# 2lboard.net
KiCad netlist of a schematic drawn in EAGLE
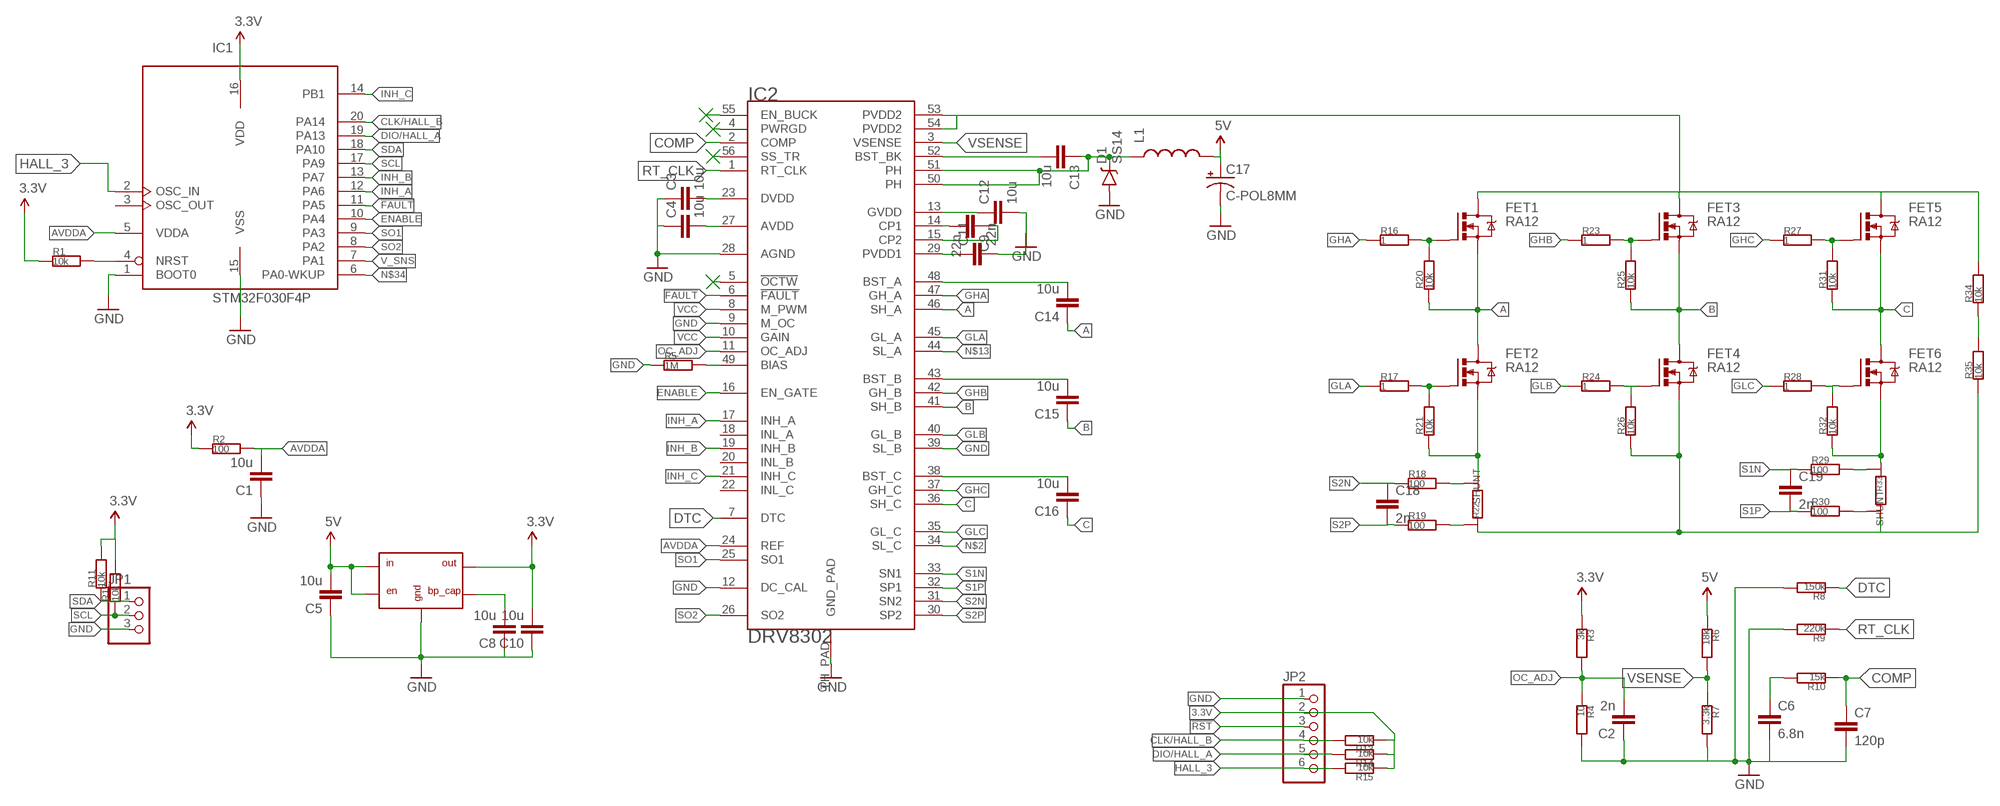
[diagram p0: schematic, sheet 1]

(export (version "E")
  (design (tool "Eeschema 10.0.6"))
  (components
    (comp (ref "C1")
      (value "10u")
      (footprint "eagle-import:C0805")
      (libsource (lib "eagle-import") (part "CC0805"))
    )
    (comp (ref "C2")
      (value "2n")
      (footprint "eagle-import:C0805")
      (libsource (lib "eagle-import") (part "CC0805"))
    )
    (comp (ref "C3")
      (value "10u")
      (footprint "eagle-import:C0805")
      (libsource (lib "eagle-import") (part "CC0805"))
    )
    (comp (ref "C4")
      (value "10u")
      (footprint "eagle-import:C0805")
      (libsource (lib "eagle-import") (part "CC0805"))
    )
    (comp (ref "C5")
      (value "10u")
      (footprint "eagle-import:C0805")
      (libsource (lib "eagle-import") (part "CC0805"))
    )
    (comp (ref "C6")
      (value "6.8n")
      (footprint "eagle-import:C0805")
      (libsource (lib "eagle-import") (part "CC0805"))
    )
    (comp (ref "C7")
      (value "120p")
      (footprint "eagle-import:C0805")
      (libsource (lib "eagle-import") (part "CC0805"))
    )
    (comp (ref "C8")
      (value "10u")
      (footprint "eagle-import:C0805")
      (libsource (lib "eagle-import") (part "CC0805"))
    )
    (comp (ref "C9")
      (value "22n")
      (footprint "eagle-import:C0805")
      (libsource (lib "eagle-import") (part "CC0805"))
    )
    (comp (ref "C10")
      (value "10u")
      (footprint "eagle-import:C0805")
      (libsource (lib "eagle-import") (part "CC0805"))
    )
    (comp (ref "C11")
      (value "22n")
      (footprint "eagle-import:C0805")
      (libsource (lib "eagle-import") (part "CC0805"))
    )
    (comp (ref "C12")
      (value "10u")
      (footprint "eagle-import:C0805")
      (libsource (lib "eagle-import") (part "CC0805"))
    )
    (comp (ref "C13")
      (value "10u")
      (footprint "eagle-import:C0805")
      (libsource (lib "eagle-import") (part "CC0805"))
    )
    (comp (ref "C14")
      (value "10u")
      (footprint "eagle-import:C0805")
      (libsource (lib "eagle-import") (part "CC0805"))
    )
    (comp (ref "C15")
      (value "10u")
      (footprint "eagle-import:C0805")
      (libsource (lib "eagle-import") (part "CC0805"))
    )
    (comp (ref "C16")
      (value "10u")
      (footprint "eagle-import:C0805")
      (libsource (lib "eagle-import") (part "CC0805"))
    )
    (comp (ref "C17")
      (value "C-POL8MM")
      (footprint "eagle-import:PCAP8")
      (libsource (lib "eagle-import") (part "C-POL8MM"))
    )
    (comp (ref "C18")
      (value "2n")
      (footprint "eagle-import:C0805")
      (libsource (lib "eagle-import") (part "CC0805"))
    )
    (comp (ref "C19")
      (value "2n")
      (footprint "eagle-import:C0805")
      (libsource (lib "eagle-import") (part "CC0805"))
    )
    (comp (ref "D1")
      (value "SS14")
      (footprint "eagle-import:SMA-DIODE")
      (libsource (lib "eagle-import") (part "SS14"))
    )
    (comp (ref "FET1")
      (value "RA12")
      (footprint "eagle-import:POWERPAK_SO8")
      (libsource (lib "eagle-import") (part "RA12"))
    )
    (comp (ref "FET2")
      (value "RA12")
      (footprint "eagle-import:POWERPAK_SO8")
      (libsource (lib "eagle-import") (part "RA12"))
    )
    (comp (ref "FET3")
      (value "RA12")
      (footprint "eagle-import:POWERPAK_SO8")
      (libsource (lib "eagle-import") (part "RA12"))
    )
    (comp (ref "FET4")
      (value "RA12")
      (footprint "eagle-import:POWERPAK_SO8")
      (libsource (lib "eagle-import") (part "RA12"))
    )
    (comp (ref "FET5")
      (value "RA12")
      (footprint "eagle-import:POWERPAK_SO8")
      (libsource (lib "eagle-import") (part "RA12"))
    )
    (comp (ref "FET6")
      (value "RA12")
      (footprint "eagle-import:POWERPAK_SO8")
      (libsource (lib "eagle-import") (part "RA12"))
    )
    (comp (ref "IC1")
      (value "STM32F030F4P")
      (footprint "eagle-import:TSSOP20-I")
      (libsource (lib "eagle-import") (part "STM32F030FP4"))
    )
    (comp (ref "IC2")
      (value "DRV8302")
      (footprint "eagle-import:HTSSOP56DCA")
      (libsource (lib "eagle-import") (part "DRV8302"))
    )
    (comp (ref "IC3")
      (value "LM258DG")
      (footprint "eagle-import:SOT23-5L")
      (libsource (lib "eagle-import") (part "LM258DG"))
    )
    (comp (ref "JP1")
      (value "PINHD-1X03_2.54")
      (footprint "eagle-import:1X03")
      (libsource (lib "eagle-import") (part "PINHD-1X03_2.54"))
    )
    (comp (ref "JP2")
      (value "PINHD-1X06_2.54")
      (footprint "eagle-import:1X06")
      (libsource (lib "eagle-import") (part "PINHD-1X06_2.54"))
    )
    (comp (ref "L1")
      (value "INDUCTORSRU1038")
      (footprint "eagle-import:SRU1038")
      (libsource (lib "eagle-import") (part "INDUCTORSRU1038"))
    )
    (comp (ref "R1")
      (value "10k")
      (footprint "eagle-import:0603")
      (libsource (lib "eagle-import") (part "R0603"))
    )
    (comp (ref "R2")
      (value "100")
      (footprint "eagle-import:0603")
      (libsource (lib "eagle-import") (part "R0603"))
    )
    (comp (ref "R3")
      (value "3k")
      (footprint "eagle-import:0603")
      (libsource (lib "eagle-import") (part "R0603"))
    )
    (comp (ref "R4")
      (value "10")
      (footprint "eagle-import:0603")
      (libsource (lib "eagle-import") (part "R0603"))
    )
    (comp (ref "R5")
      (value "1M")
      (footprint "eagle-import:0603")
      (libsource (lib "eagle-import") (part "R0603"))
    )
    (comp (ref "R6")
      (value "18k")
      (footprint "eagle-import:0603")
      (libsource (lib "eagle-import") (part "R0603"))
    )
    (comp (ref "R7")
      (value "3.3k")
      (footprint "eagle-import:0603")
      (libsource (lib "eagle-import") (part "R0603"))
    )
    (comp (ref "R8")
      (value "150k")
      (footprint "eagle-import:0603")
      (libsource (lib "eagle-import") (part "R0603"))
    )
    (comp (ref "R9")
      (value "220k")
      (footprint "eagle-import:0603")
      (libsource (lib "eagle-import") (part "R0603"))
    )
    (comp (ref "R10")
      (value "15k")
      (footprint "eagle-import:0603")
      (libsource (lib "eagle-import") (part "R0603"))
    )
    (comp (ref "R11")
      (value "10k")
      (footprint "eagle-import:0603")
      (libsource (lib "eagle-import") (part "R0603"))
    )
    (comp (ref "R12")
      (value "10k")
      (footprint "eagle-import:0603")
      (libsource (lib "eagle-import") (part "R0603"))
    )
    (comp (ref "R13")
      (value "10k")
      (footprint "eagle-import:0603")
      (libsource (lib "eagle-import") (part "R0603"))
    )
    (comp (ref "R14")
      (value "10k")
      (footprint "eagle-import:0603")
      (libsource (lib "eagle-import") (part "R0603"))
    )
    (comp (ref "R15")
      (value "10k")
      (footprint "eagle-import:0603")
      (libsource (lib "eagle-import") (part "R0603"))
    )
    (comp (ref "R16")
      (value "1")
      (footprint "eagle-import:0603")
      (libsource (lib "eagle-import") (part "R0603"))
    )
    (comp (ref "R17")
      (value "1")
      (footprint "eagle-import:0603")
      (libsource (lib "eagle-import") (part "R0603"))
    )
    (comp (ref "R18")
      (value "100")
      (footprint "eagle-import:0603")
      (libsource (lib "eagle-import") (part "R0603"))
    )
    (comp (ref "R19")
      (value "100")
      (footprint "eagle-import:0603")
      (libsource (lib "eagle-import") (part "R0603"))
    )
    (comp (ref "R20")
      (value "10k")
      (footprint "eagle-import:0603")
      (libsource (lib "eagle-import") (part "R0603"))
    )
    (comp (ref "R21")
      (value "10k")
      (footprint "eagle-import:0603")
      (libsource (lib "eagle-import") (part "R0603"))
    )
    (comp (ref "R22")
      (value "SHUNT")
      (footprint "eagle-import:SHUNT")
      (libsource (lib "eagle-import") (part "SHUNT"))
    )
    (comp (ref "R23")
      (value "1")
      (footprint "eagle-import:0603")
      (libsource (lib "eagle-import") (part "R0603"))
    )
    (comp (ref "R24")
      (value "1")
      (footprint "eagle-import:0603")
      (libsource (lib "eagle-import") (part "R0603"))
    )
    (comp (ref "R25")
      (value "10k")
      (footprint "eagle-import:0603")
      (libsource (lib "eagle-import") (part "R0603"))
    )
    (comp (ref "R26")
      (value "10k")
      (footprint "eagle-import:0603")
      (libsource (lib "eagle-import") (part "R0603"))
    )
    (comp (ref "R27")
      (value "1")
      (footprint "eagle-import:0603")
      (libsource (lib "eagle-import") (part "R0603"))
    )
    (comp (ref "R28")
      (value "1")
      (footprint "eagle-import:0603")
      (libsource (lib "eagle-import") (part "R0603"))
    )
    (comp (ref "R29")
      (value "100")
      (footprint "eagle-import:0603")
      (libsource (lib "eagle-import") (part "R0603"))
    )
    (comp (ref "R30")
      (value "100")
      (footprint "eagle-import:0603")
      (libsource (lib "eagle-import") (part "R0603"))
    )
    (comp (ref "R31")
      (value "10k")
      (footprint "eagle-import:0603")
      (libsource (lib "eagle-import") (part "R0603"))
    )
    (comp (ref "R32")
      (value "10k")
      (footprint "eagle-import:0603")
      (libsource (lib "eagle-import") (part "R0603"))
    )
    (comp (ref "R33")
      (value "SHUNT")
      (footprint "eagle-import:SHUNT")
      (libsource (lib "eagle-import") (part "SHUNT"))
    )
    (comp (ref "R34")
      (value "10k")
      (footprint "eagle-import:0603")
      (libsource (lib "eagle-import") (part "R0603"))
    )
    (comp (ref "R35")
      (value "10k")
      (footprint "eagle-import:0603")
      (libsource (lib "eagle-import") (part "R0603"))
    )
  )
  (nets
    (net (code "1") (name "/~{FAULT}") (class "Default")
      (node (ref "IC1") (pin "11") (pinfunction "PA5_11") (pintype "bidirectional"))
      (node (ref "IC2") (pin "6") (pinfunction "~{FAULT}_6") (pintype "bidirectional"))
    )
    (net (code "2") (name "/~{RST}") (class "Default")
      (node (ref "IC1") (pin "4") (pinfunction "NRST_4") (pintype "bidirectional"))
      (node (ref "JP2") (pin "3") (pinfunction "3_3") (pintype "passive"))
      (node (ref "R1") (pin "2") (pinfunction "2_2") (pintype "passive"))
    )
    (net (code "3") (name "3.3V") (class "Default")
      (node (ref "C10") (pin "2") (pinfunction "2_2") (pintype "passive"))
      (node (ref "IC1") (pin "16") (pinfunction "VDD_16") (pintype "power_in"))
      (node (ref "IC3") (pin "5") (pinfunction "OUT_5") (pintype "bidirectional"))
      (node (ref "JP2") (pin "2") (pinfunction "2_2") (pintype "passive"))
      (node (ref "R1") (pin "1") (pinfunction "1_1") (pintype "passive"))
      (node (ref "R11") (pin "2") (pinfunction "2_2") (pintype "passive"))
      (node (ref "R12") (pin "2") (pinfunction "2_2") (pintype "passive"))
      (node (ref "R13") (pin "1") (pinfunction "1_1") (pintype "passive"))
      (node (ref "R14") (pin "1") (pinfunction "1_1") (pintype "passive"))
      (node (ref "R15") (pin "1") (pinfunction "1_1") (pintype "passive"))
      (node (ref "R2") (pin "1") (pinfunction "1_1") (pintype "passive"))
      (node (ref "R3") (pin "1") (pinfunction "1_1") (pintype "passive"))
    )
    (net (code "4") (name "5V") (class "Default")
      (node (ref "C17") (pin "P$1") (pinfunction "+_P$1") (pintype "passive"))
      (node (ref "C5") (pin "2") (pinfunction "2_2") (pintype "passive"))
      (node (ref "IC3") (pin "1") (pinfunction "IN_1") (pintype "bidirectional"))
      (node (ref "IC3") (pin "3") (pinfunction "EN_3") (pintype "bidirectional"))
      (node (ref "L1") (pin "2") (pinfunction "2_2") (pintype "passive"))
      (node (ref "R6") (pin "1") (pinfunction "1_1") (pintype "passive"))
    )
    (net (code "5") (name "A") (class "Default")
      (node (ref "C14") (pin "1") (pinfunction "1_1") (pintype "passive"))
      (node (ref "FET1") (pin "1") (pinfunction "S_1") (pintype "passive"))
      (node (ref "FET1") (pin "2") (pinfunction "S_2") (pintype "passive"))
      (node (ref "FET1") (pin "3") (pinfunction "S_3") (pintype "passive"))
      (node (ref "FET2") (pin "5") (pinfunction "D_5") (pintype "passive"))
      (node (ref "FET2") (pin "6") (pinfunction "D_6") (pintype "passive"))
      (node (ref "FET2") (pin "7") (pinfunction "D_7") (pintype "passive"))
      (node (ref "FET2") (pin "8") (pinfunction "D_8") (pintype "passive"))
      (node (ref "FET2") (pin "P$1") (pinfunction "D_P$1") (pintype "passive"))
      (node (ref "IC2") (pin "46") (pinfunction "SH_A_46") (pintype "bidirectional"))
      (node (ref "R20") (pin "1") (pinfunction "1_1") (pintype "passive"))
    )
    (net (code "6") (name "AVDDA") (class "Default")
      (node (ref "C1") (pin "2") (pinfunction "2_2") (pintype "passive"))
      (node (ref "IC1") (pin "5") (pinfunction "VDDA_5") (pintype "power_in"))
      (node (ref "IC2") (pin "24") (pinfunction "REF_24") (pintype "bidirectional"))
      (node (ref "R2") (pin "2") (pinfunction "2_2") (pintype "passive"))
    )
    (net (code "7") (name "B") (class "Default")
      (node (ref "C15") (pin "1") (pinfunction "1_1") (pintype "passive"))
      (node (ref "FET3") (pin "1") (pinfunction "S_1") (pintype "passive"))
      (node (ref "FET3") (pin "2") (pinfunction "S_2") (pintype "passive"))
      (node (ref "FET3") (pin "3") (pinfunction "S_3") (pintype "passive"))
      (node (ref "FET4") (pin "5") (pinfunction "D_5") (pintype "passive"))
      (node (ref "FET4") (pin "6") (pinfunction "D_6") (pintype "passive"))
      (node (ref "FET4") (pin "7") (pinfunction "D_7") (pintype "passive"))
      (node (ref "FET4") (pin "8") (pinfunction "D_8") (pintype "passive"))
      (node (ref "FET4") (pin "P$1") (pinfunction "D_P$1") (pintype "passive"))
      (node (ref "IC2") (pin "41") (pinfunction "SH_B_41") (pintype "bidirectional"))
      (node (ref "R25") (pin "1") (pinfunction "1_1") (pintype "passive"))
    )
    (net (code "8") (name "C") (class "Default")
      (node (ref "C16") (pin "1") (pinfunction "1_1") (pintype "passive"))
      (node (ref "FET5") (pin "1") (pinfunction "S_1") (pintype "passive"))
      (node (ref "FET5") (pin "2") (pinfunction "S_2") (pintype "passive"))
      (node (ref "FET5") (pin "3") (pinfunction "S_3") (pintype "passive"))
      (node (ref "FET6") (pin "5") (pinfunction "D_5") (pintype "passive"))
      (node (ref "FET6") (pin "6") (pinfunction "D_6") (pintype "passive"))
      (node (ref "FET6") (pin "7") (pinfunction "D_7") (pintype "passive"))
      (node (ref "FET6") (pin "8") (pinfunction "D_8") (pintype "passive"))
      (node (ref "FET6") (pin "P$1") (pinfunction "D_P$1") (pintype "passive"))
      (node (ref "IC2") (pin "36") (pinfunction "SH_C_36") (pintype "bidirectional"))
      (node (ref "R31") (pin "1") (pinfunction "1_1") (pintype "passive"))
    )
    (net (code "9") (name "CLK{slash}HALL_B") (class "Default")
      (node (ref "IC1") (pin "20") (pinfunction "PA14_20") (pintype "bidirectional"))
      (node (ref "JP2") (pin "4") (pinfunction "4_4") (pintype "passive"))
      (node (ref "R13") (pin "2") (pinfunction "2_2") (pintype "passive"))
    )
    (net (code "10") (name "COMP") (class "Default")
      (node (ref "C7") (pin "1") (pinfunction "1_1") (pintype "passive"))
      (node (ref "IC2") (pin "2") (pinfunction "COMP_2") (pintype "bidirectional"))
      (node (ref "R10") (pin "1") (pinfunction "1_1") (pintype "passive"))
    )
    (net (code "11") (name "DIO{slash}HALL_A") (class "Default")
      (node (ref "IC1") (pin "19") (pinfunction "PA13_19") (pintype "bidirectional"))
      (node (ref "JP2") (pin "5") (pinfunction "5_5") (pintype "passive"))
      (node (ref "R14") (pin "2") (pinfunction "2_2") (pintype "passive"))
    )
    (net (code "12") (name "DTC") (class "Default")
      (node (ref "IC2") (pin "7") (pinfunction "DTC_7") (pintype "bidirectional"))
      (node (ref "R8") (pin "1") (pinfunction "1_1") (pintype "passive"))
    )
    (net (code "13") (name "ENABLE") (class "Default")
      (node (ref "IC1") (pin "10") (pinfunction "PA4_10") (pintype "bidirectional"))
      (node (ref "IC2") (pin "16") (pinfunction "EN_GATE_16") (pintype "bidirectional"))
    )
    (net (code "14") (name "GHA") (class "Default")
      (node (ref "IC2") (pin "47") (pinfunction "GH_A_47") (pintype "bidirectional"))
      (node (ref "R16") (pin "1") (pinfunction "1_1") (pintype "passive"))
    )
    (net (code "15") (name "GHB") (class "Default")
      (node (ref "IC2") (pin "42") (pinfunction "GH_B_42") (pintype "bidirectional"))
      (node (ref "R23") (pin "1") (pinfunction "1_1") (pintype "passive"))
    )
    (net (code "16") (name "GHC") (class "Default")
      (node (ref "IC2") (pin "37") (pinfunction "GH_C_37") (pintype "bidirectional"))
      (node (ref "R27") (pin "1") (pinfunction "1_1") (pintype "passive"))
    )
    (net (code "17") (name "GLA") (class "Default")
      (node (ref "IC2") (pin "45") (pinfunction "GL_A_45") (pintype "bidirectional"))
      (node (ref "R17") (pin "1") (pinfunction "1_1") (pintype "passive"))
    )
    (net (code "18") (name "GLB") (class "Default")
      (node (ref "IC2") (pin "40") (pinfunction "GL_B_40") (pintype "bidirectional"))
      (node (ref "R24") (pin "1") (pinfunction "1_1") (pintype "passive"))
    )
    (net (code "19") (name "GLC") (class "Default")
      (node (ref "IC2") (pin "35") (pinfunction "GL_C_35") (pintype "bidirectional"))
      (node (ref "R28") (pin "1") (pinfunction "1_1") (pintype "passive"))
    )
    (net (code "20") (name "GND") (class "Default")
      (node (ref "C1") (pin "1") (pinfunction "1_1") (pintype "passive"))
      (node (ref "C10") (pin "1") (pinfunction "1_1") (pintype "passive"))
      (node (ref "C11") (pin "2") (pinfunction "2_2") (pintype "passive"))
      (node (ref "C12") (pin "2") (pinfunction "2_2") (pintype "passive"))
      (node (ref "C17") (pin "P$2") (pinfunction "-_P$2") (pintype "passive"))
      (node (ref "C2") (pin "1") (pinfunction "1_1") (pintype "passive"))
      (node (ref "C3") (pin "1") (pinfunction "1_1") (pintype "passive"))
      (node (ref "C4") (pin "1") (pinfunction "1_1") (pintype "passive"))
      (node (ref "C5") (pin "1") (pinfunction "1_1") (pintype "passive"))
      (node (ref "C6") (pin "2") (pinfunction "2_2") (pintype "passive"))
      (node (ref "C7") (pin "2") (pinfunction "2_2") (pintype "passive"))
      (node (ref "C8") (pin "1") (pinfunction "1_1") (pintype "passive"))
      (node (ref "D1") (pin "A") (pinfunction "A_A") (pintype "passive"))
      (node (ref "FET4") (pin "1") (pinfunction "S_1") (pintype "passive"))
      (node (ref "FET4") (pin "2") (pinfunction "S_2") (pintype "passive"))
      (node (ref "FET4") (pin "3") (pinfunction "S_3") (pintype "passive"))
      (node (ref "IC1") (pin "1") (pinfunction "BOOT0_1") (pintype "input"))
      (node (ref "IC1") (pin "15") (pinfunction "VSS_15") (pintype "power_in"))
      (node (ref "IC2") (pin "12") (pinfunction "DC_CAL_12") (pintype "bidirectional"))
      (node (ref "IC2") (pin "28") (pinfunction "AGND_28") (pintype "bidirectional"))
      (node (ref "IC2") (pin "39") (pinfunction "SL_B_39") (pintype "bidirectional"))
      (node (ref "IC2") (pin "9") (pinfunction "M_OC_9") (pintype "bidirectional"))
      (node (ref "IC2") (pin "TH_PAD") (pinfunction "GND_PAD_TH_PAD") (pintype "bidirectional"))
      (node (ref "IC3") (pin "2") (pinfunction "GND_2") (pintype "bidirectional"))
      (node (ref "JP1") (pin "3") (pinfunction "3_3") (pintype "passive"))
      (node (ref "JP2") (pin "1") (pinfunction "1_1") (pintype "passive"))
      (node (ref "R22") (pin "P$1") (pinfunction "1_P$1") (pintype "passive"))
      (node (ref "R26") (pin "1") (pinfunction "1_1") (pintype "passive"))
      (node (ref "R33") (pin "P$2") (pinfunction "2_P$2") (pintype "passive"))
      (node (ref "R35") (pin "1") (pinfunction "1_1") (pintype "passive"))
      (node (ref "R4") (pin "2") (pinfunction "2_2") (pintype "passive"))
      (node (ref "R5") (pin "1") (pinfunction "1_1") (pintype "passive"))
      (node (ref "R7") (pin "2") (pinfunction "2_2") (pintype "passive"))
      (node (ref "R8") (pin "2") (pinfunction "2_2") (pintype "passive"))
      (node (ref "R9") (pin "2") (pinfunction "2_2") (pintype "passive"))
    )
    (net (code "21") (name "HALL_3") (class "Default")
      (node (ref "IC1") (pin "2") (pinfunction "OSC_IN_2") (pintype "bidirectional"))
      (node (ref "JP2") (pin "6") (pinfunction "6_6") (pintype "passive"))
      (node (ref "R15") (pin "2") (pinfunction "2_2") (pintype "passive"))
    )
    (net (code "22") (name "INH_A") (class "Default")
      (node (ref "IC1") (pin "12") (pinfunction "PA6_12") (pintype "bidirectional"))
      (node (ref "IC2") (pin "17") (pinfunction "INH_A_17") (pintype "bidirectional"))
    )
    (net (code "23") (name "INH_B") (class "Default")
      (node (ref "IC1") (pin "13") (pinfunction "PA7_13") (pintype "bidirectional"))
      (node (ref "IC2") (pin "19") (pinfunction "INH_B_19") (pintype "bidirectional"))
    )
    (net (code "24") (name "INH_C") (class "Default")
      (node (ref "IC1") (pin "14") (pinfunction "PB1_14") (pintype "bidirectional"))
      (node (ref "IC2") (pin "21") (pinfunction "INH_C_21") (pintype "bidirectional"))
    )
    (net (code "25") (name "N$2") (class "Default")
      (node (ref "FET6") (pin "1") (pinfunction "S_1") (pintype "passive"))
      (node (ref "FET6") (pin "2") (pinfunction "S_2") (pintype "passive"))
      (node (ref "FET6") (pin "3") (pinfunction "S_3") (pintype "passive"))
      (node (ref "IC2") (pin "34") (pinfunction "SL_C_34") (pintype "bidirectional"))
      (node (ref "R32") (pin "1") (pinfunction "1_1") (pintype "passive"))
      (node (ref "R33") (pin "P$1") (pinfunction "1_P$1") (pintype "passive"))
    )
    (net (code "26") (name "N$13") (class "Default")
      (node (ref "FET2") (pin "1") (pinfunction "S_1") (pintype "passive"))
      (node (ref "FET2") (pin "2") (pinfunction "S_2") (pintype "passive"))
      (node (ref "FET2") (pin "3") (pinfunction "S_3") (pintype "passive"))
      (node (ref "IC2") (pin "44") (pinfunction "SL_A_44") (pintype "bidirectional"))
      (node (ref "R21") (pin "1") (pinfunction "1_1") (pintype "passive"))
      (node (ref "R22") (pin "P$2") (pinfunction "2_P$2") (pintype "passive"))
    )
    (net (code "27") (name "N$34") (class "Default")
      (node (ref "IC1") (pin "6") (pinfunction "PA0-WKUP_6") (pintype "bidirectional"))
    )
    (net (code "28") (name "Net-(C6-Pad1)") (class "Default")
      (node (ref "C6") (pin "1") (pinfunction "1_1") (pintype "passive"))
      (node (ref "R10") (pin "2") (pinfunction "2_2") (pintype "passive"))
    )
    (net (code "29") (name "Net-(C13-Pad1)") (class "Default")
      (node (ref "C13") (pin "1") (pinfunction "1_1") (pintype "passive"))
      (node (ref "D1") (pin "C") (pinfunction "C_C") (pintype "passive"))
      (node (ref "IC2") (pin "50") (pinfunction "PH_50") (pintype "bidirectional"))
      (node (ref "IC2") (pin "51") (pinfunction "PH_51") (pintype "bidirectional"))
      (node (ref "L1") (pin "1") (pinfunction "1_1") (pintype "passive"))
    )
    (net (code "30") (name "Net-(FET1-G)") (class "Default")
      (node (ref "FET1") (pin "4") (pinfunction "G_4") (pintype "passive"))
      (node (ref "R16") (pin "2") (pinfunction "2_2") (pintype "passive"))
      (node (ref "R20") (pin "2") (pinfunction "2_2") (pintype "passive"))
    )
    (net (code "31") (name "Net-(FET2-G)") (class "Default")
      (node (ref "FET2") (pin "4") (pinfunction "G_4") (pintype "passive"))
      (node (ref "R17") (pin "2") (pinfunction "2_2") (pintype "passive"))
      (node (ref "R21") (pin "2") (pinfunction "2_2") (pintype "passive"))
    )
    (net (code "32") (name "Net-(FET3-G)") (class "Default")
      (node (ref "FET3") (pin "4") (pinfunction "G_4") (pintype "passive"))
      (node (ref "R23") (pin "2") (pinfunction "2_2") (pintype "passive"))
      (node (ref "R25") (pin "2") (pinfunction "2_2") (pintype "passive"))
    )
    (net (code "33") (name "Net-(FET4-G)") (class "Default")
      (node (ref "FET4") (pin "4") (pinfunction "G_4") (pintype "passive"))
      (node (ref "R24") (pin "2") (pinfunction "2_2") (pintype "passive"))
      (node (ref "R26") (pin "2") (pinfunction "2_2") (pintype "passive"))
    )
    (net (code "34") (name "Net-(FET5-G)") (class "Default")
      (node (ref "FET5") (pin "4") (pinfunction "G_4") (pintype "passive"))
      (node (ref "R27") (pin "2") (pinfunction "2_2") (pintype "passive"))
      (node (ref "R31") (pin "2") (pinfunction "2_2") (pintype "passive"))
    )
    (net (code "35") (name "Net-(FET6-G)") (class "Default")
      (node (ref "FET6") (pin "4") (pinfunction "G_4") (pintype "passive"))
      (node (ref "R28") (pin "2") (pinfunction "2_2") (pintype "passive"))
      (node (ref "R32") (pin "2") (pinfunction "2_2") (pintype "passive"))
    )
    (net (code "36") (name "Net-(IC2-AVDD)") (class "Default")
      (node (ref "C4") (pin "2") (pinfunction "2_2") (pintype "passive"))
      (node (ref "IC2") (pin "27") (pinfunction "AVDD_27") (pintype "bidirectional"))
    )
    (net (code "37") (name "Net-(IC2-BIAS)") (class "Default")
      (node (ref "IC2") (pin "49") (pinfunction "BIAS_49") (pintype "bidirectional"))
      (node (ref "R5") (pin "2") (pinfunction "2_2") (pintype "passive"))
    )
    (net (code "38") (name "Net-(IC2-BST_A)") (class "Default")
      (node (ref "C14") (pin "2") (pinfunction "2_2") (pintype "passive"))
      (node (ref "IC2") (pin "48") (pinfunction "BST_A_48") (pintype "bidirectional"))
    )
    (net (code "39") (name "Net-(IC2-BST_B)") (class "Default")
      (node (ref "C15") (pin "2") (pinfunction "2_2") (pintype "passive"))
      (node (ref "IC2") (pin "43") (pinfunction "BST_B_43") (pintype "bidirectional"))
    )
    (net (code "40") (name "Net-(IC2-BST_BK)") (class "Default")
      (node (ref "C13") (pin "2") (pinfunction "2_2") (pintype "passive"))
      (node (ref "IC2") (pin "52") (pinfunction "BST_BK_52") (pintype "bidirectional"))
    )
    (net (code "41") (name "Net-(IC2-BST_C)") (class "Default")
      (node (ref "C16") (pin "2") (pinfunction "2_2") (pintype "passive"))
      (node (ref "IC2") (pin "38") (pinfunction "BST_C_38") (pintype "bidirectional"))
    )
    (net (code "42") (name "Net-(IC2-CP1)") (class "Default")
      (node (ref "C9") (pin "2") (pinfunction "2_2") (pintype "passive"))
      (node (ref "IC2") (pin "14") (pinfunction "CP1_14") (pintype "bidirectional"))
    )
    (net (code "43") (name "Net-(IC2-CP2)") (class "Default")
      (node (ref "C9") (pin "1") (pinfunction "1_1") (pintype "passive"))
      (node (ref "IC2") (pin "15") (pinfunction "CP2_15") (pintype "bidirectional"))
    )
    (net (code "44") (name "Net-(IC2-DVDD)") (class "Default")
      (node (ref "C3") (pin "2") (pinfunction "2_2") (pintype "passive"))
      (node (ref "IC2") (pin "23") (pinfunction "DVDD_23") (pintype "bidirectional"))
    )
    (net (code "45") (name "Net-(IC2-GVDD)") (class "Default")
      (node (ref "C12") (pin "1") (pinfunction "1_1") (pintype "passive"))
      (node (ref "IC2") (pin "13") (pinfunction "GVDD_13") (pintype "bidirectional"))
    )
    (net (code "46") (name "Net-(IC2-PVDD1)") (class "Default")
      (node (ref "C11") (pin "1") (pinfunction "1_1") (pintype "passive"))
      (node (ref "IC2") (pin "29") (pinfunction "PVDD1_29") (pintype "bidirectional"))
    )
    (net (code "47") (name "Net-(IC3-CAP)") (class "Default")
      (node (ref "C8") (pin "2") (pinfunction "2_2") (pintype "passive"))
      (node (ref "IC3") (pin "4") (pinfunction "CAP_4") (pintype "bidirectional"))
    )
    (net (code "48") (name "Net-(R22-P$1)") (class "Default")
      (node (ref "R19") (pin "2") (pinfunction "2_2") (pintype "passive"))
      (node (ref "R22") (pin "P$3") (pinfunction "P$1_P$3") (pintype "bidirectional"))
    )
    (net (code "49") (name "Net-(R22-P$2)") (class "Default")
      (node (ref "R18") (pin "2") (pinfunction "2_2") (pintype "passive"))
      (node (ref "R22") (pin "P$4") (pinfunction "P$2_P$4") (pintype "bidirectional"))
    )
    (net (code "50") (name "Net-(R33-P$1)") (class "Default")
      (node (ref "R29") (pin "2") (pinfunction "2_2") (pintype "passive"))
      (node (ref "R33") (pin "P$3") (pinfunction "P$1_P$3") (pintype "bidirectional"))
    )
    (net (code "51") (name "Net-(R33-P$2)") (class "Default")
      (node (ref "R30") (pin "2") (pinfunction "2_2") (pintype "passive"))
      (node (ref "R33") (pin "P$4") (pinfunction "P$2_P$4") (pintype "bidirectional"))
    )
    (net (code "52") (name "OC_ADJ") (class "Default")
      (node (ref "C2") (pin "2") (pinfunction "2_2") (pintype "passive"))
      (node (ref "IC2") (pin "11") (pinfunction "OC_ADJ_11") (pintype "bidirectional"))
      (node (ref "R3") (pin "2") (pinfunction "2_2") (pintype "passive"))
      (node (ref "R4") (pin "1") (pinfunction "1_1") (pintype "passive"))
    )
    (net (code "53") (name "RT_CLK") (class "Default")
      (node (ref "IC2") (pin "1") (pinfunction "RT_CLK_1") (pintype "bidirectional"))
      (node (ref "R9") (pin "1") (pinfunction "1_1") (pintype "passive"))
    )
    (net (code "54") (name "S1N") (class "Default")
      (node (ref "C19") (pin "1") (pinfunction "1_1") (pintype "passive"))
      (node (ref "IC2") (pin "33") (pinfunction "SN1_33") (pintype "bidirectional"))
      (node (ref "R29") (pin "1") (pinfunction "1_1") (pintype "passive"))
    )
    (net (code "55") (name "S1P") (class "Default")
      (node (ref "C19") (pin "2") (pinfunction "2_2") (pintype "passive"))
      (node (ref "IC2") (pin "32") (pinfunction "SP1_32") (pintype "bidirectional"))
      (node (ref "R30") (pin "1") (pinfunction "1_1") (pintype "passive"))
    )
    (net (code "56") (name "S2N") (class "Default")
      (node (ref "C18") (pin "1") (pinfunction "1_1") (pintype "passive"))
      (node (ref "IC2") (pin "31") (pinfunction "SN2_31") (pintype "bidirectional"))
      (node (ref "R18") (pin "1") (pinfunction "1_1") (pintype "passive"))
    )
    (net (code "57") (name "S2P") (class "Default")
      (node (ref "C18") (pin "2") (pinfunction "2_2") (pintype "passive"))
      (node (ref "IC2") (pin "30") (pinfunction "SP2_30") (pintype "bidirectional"))
      (node (ref "R19") (pin "1") (pinfunction "1_1") (pintype "passive"))
    )
    (net (code "58") (name "SCL") (class "Default")
      (node (ref "IC1") (pin "17") (pinfunction "PA9_17") (pintype "bidirectional"))
      (node (ref "JP1") (pin "2") (pinfunction "2_2") (pintype "passive"))
      (node (ref "R12") (pin "1") (pinfunction "1_1") (pintype "passive"))
    )
    (net (code "59") (name "SDA") (class "Default")
      (node (ref "IC1") (pin "18") (pinfunction "PA10_18") (pintype "bidirectional"))
      (node (ref "JP1") (pin "1") (pinfunction "1_1") (pintype "passive"))
      (node (ref "R11") (pin "1") (pinfunction "1_1") (pintype "passive"))
    )
    (net (code "60") (name "SO1") (class "Default")
      (node (ref "IC1") (pin "9") (pinfunction "PA3_9") (pintype "bidirectional"))
      (node (ref "IC2") (pin "25") (pinfunction "SO1_25") (pintype "bidirectional"))
    )
    (net (code "61") (name "SO2") (class "Default")
      (node (ref "IC1") (pin "8") (pinfunction "PA2_8") (pintype "bidirectional"))
      (node (ref "IC2") (pin "26") (pinfunction "SO2_26") (pintype "bidirectional"))
    )
    (net (code "62") (name "VCC") (class "Default")
      (node (ref "FET1") (pin "5") (pinfunction "D_5") (pintype "passive"))
      (node (ref "FET1") (pin "6") (pinfunction "D_6") (pintype "passive"))
      (node (ref "FET1") (pin "7") (pinfunction "D_7") (pintype "passive"))
      (node (ref "FET1") (pin "8") (pinfunction "D_8") (pintype "passive"))
      (node (ref "FET1") (pin "P$1") (pinfunction "D_P$1") (pintype "passive"))
      (node (ref "FET3") (pin "5") (pinfunction "D_5") (pintype "passive"))
      (node (ref "FET3") (pin "6") (pinfunction "D_6") (pintype "passive"))
      (node (ref "FET3") (pin "7") (pinfunction "D_7") (pintype "passive"))
      (node (ref "FET3") (pin "8") (pinfunction "D_8") (pintype "passive"))
      (node (ref "FET3") (pin "P$1") (pinfunction "D_P$1") (pintype "passive"))
      (node (ref "FET5") (pin "5") (pinfunction "D_5") (pintype "passive"))
      (node (ref "FET5") (pin "6") (pinfunction "D_6") (pintype "passive"))
      (node (ref "FET5") (pin "7") (pinfunction "D_7") (pintype "passive"))
      (node (ref "FET5") (pin "8") (pinfunction "D_8") (pintype "passive"))
      (node (ref "FET5") (pin "P$1") (pinfunction "D_P$1") (pintype "passive"))
      (node (ref "IC2") (pin "10") (pinfunction "GAIN_10") (pintype "bidirectional"))
      (node (ref "IC2") (pin "53") (pinfunction "PVDD2_53") (pintype "bidirectional"))
      (node (ref "IC2") (pin "54") (pinfunction "PVDD2_54") (pintype "bidirectional"))
      (node (ref "IC2") (pin "8") (pinfunction "M_PWM_8") (pintype "bidirectional"))
      (node (ref "R34") (pin "2") (pinfunction "2_2") (pintype "passive"))
    )
    (net (code "63") (name "VSENSE") (class "Default")
      (node (ref "IC2") (pin "3") (pinfunction "VSENSE_3") (pintype "bidirectional"))
      (node (ref "R6") (pin "2") (pinfunction "2_2") (pintype "passive"))
      (node (ref "R7") (pin "1") (pinfunction "1_1") (pintype "passive"))
    )
    (net (code "64") (name "V_SNS") (class "Default")
      (node (ref "IC1") (pin "7") (pinfunction "PA1_7") (pintype "bidirectional"))
      (node (ref "R34") (pin "1") (pinfunction "1_1") (pintype "passive"))
      (node (ref "R35") (pin "2") (pinfunction "2_2") (pintype "passive"))
    )
    (net (code "65") (name "unconnected-(IC1A-OSC_OUT-Pad3)") (class "Default")
      (node (ref "IC1") (pin "3") (pinfunction "OSC_OUT_3") (pintype "bidirectional"))
    )
    (net (code "66") (name "unconnected-(IC2-EN_BUCK-Pad55)") (class "Default")
      (node (ref "IC2") (pin "55") (pinfunction "EN_BUCK_55") (pintype "bidirectional"))
    )
    (net (code "67") (name "unconnected-(IC2-INL_A-Pad18)") (class "Default")
      (node (ref "IC2") (pin "18") (pinfunction "INL_A_18") (pintype "bidirectional"))
    )
    (net (code "68") (name "unconnected-(IC2-INL_B-Pad20)") (class "Default")
      (node (ref "IC2") (pin "20") (pinfunction "INL_B_20") (pintype "bidirectional"))
    )
    (net (code "69") (name "unconnected-(IC2-INL_C-Pad22)") (class "Default")
      (node (ref "IC2") (pin "22") (pinfunction "INL_C_22") (pintype "bidirectional"))
    )
    (net (code "70") (name "unconnected-(IC2-PWRGD-Pad4)") (class "Default")
      (node (ref "IC2") (pin "4") (pinfunction "PWRGD_4") (pintype "bidirectional"))
    )
    (net (code "71") (name "unconnected-(IC2-SS_TR-Pad56)") (class "Default")
      (node (ref "IC2") (pin "56") (pinfunction "SS_TR_56") (pintype "bidirectional"))
    )
    (net (code "72") (name "unconnected-(IC2-~{OCTW}-Pad5)") (class "Default")
      (node (ref "IC2") (pin "5") (pinfunction "~{OCTW}_5") (pintype "bidirectional"))
    )
  )
)
